# Sheet1.net
KiCad netlist of a schematic drawn in Altium Designer
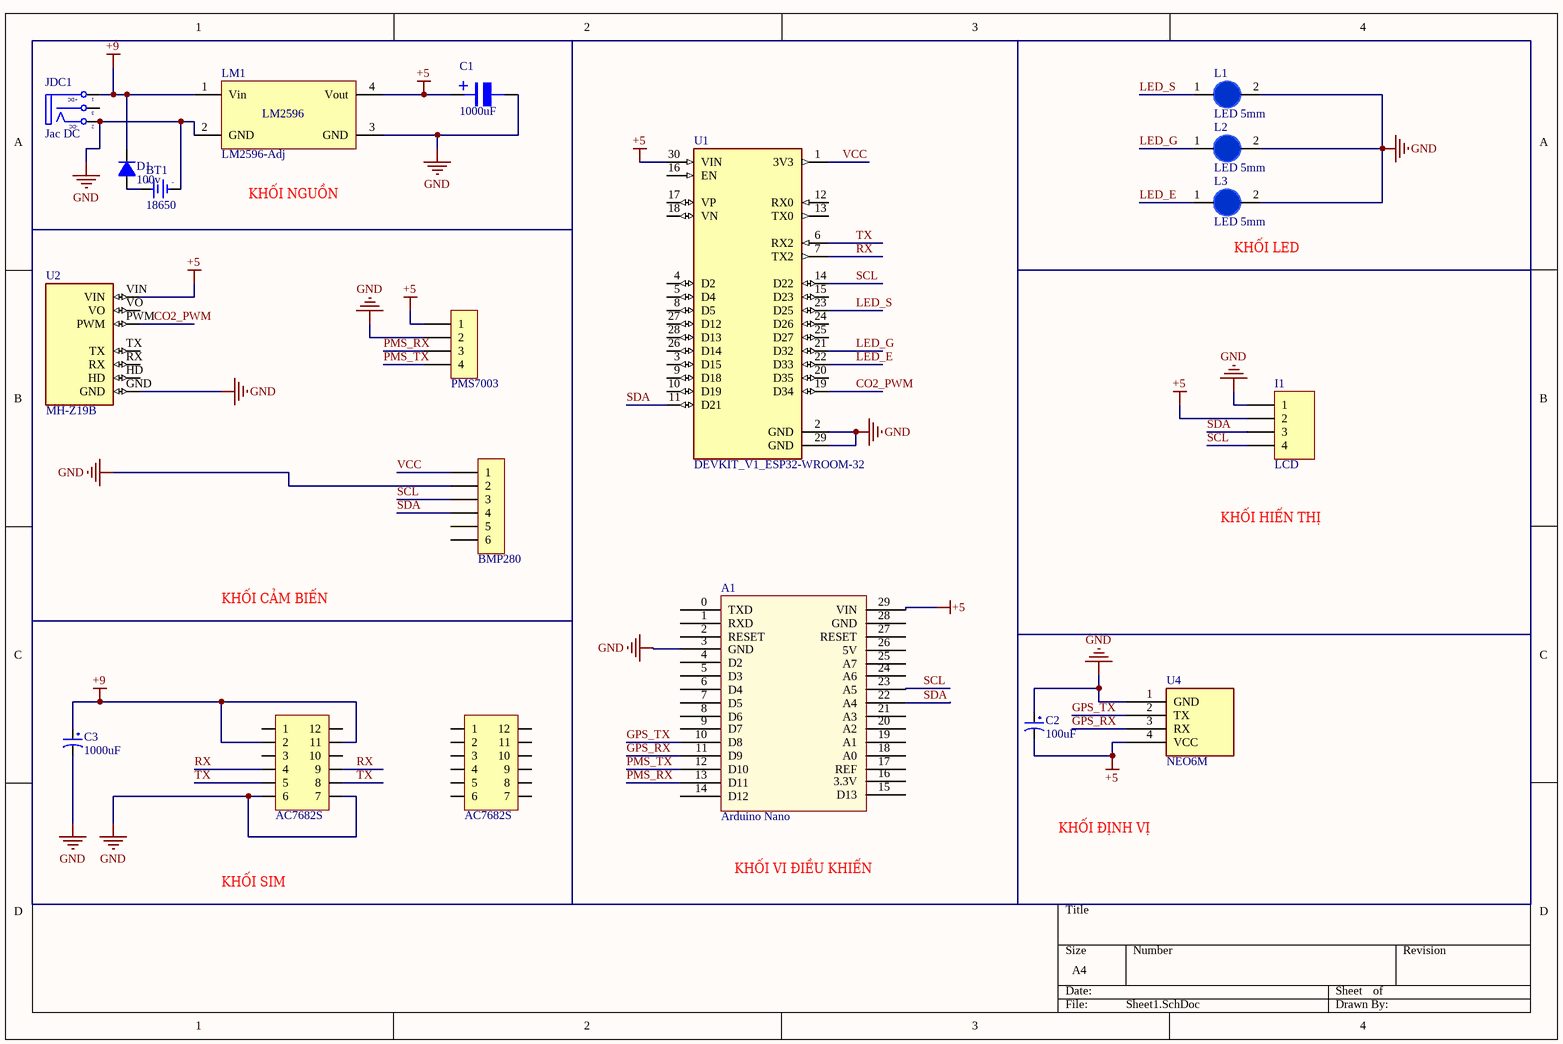
[diagram p0: Sheet1.SchDoc]

(export (version "E")
  (design (tool "Eeschema 10.0.6"))
  (components
    (comp (ref "A1")
      (value "Arduino Nano")
      (footprint "Arduino Nano")
      (libsource (lib "KhanhBK_Library_4") (part "Arduino Nano"))
    )
    (comp (ref "BT1")
      (value "18650")
      (footprint "DE PIN 18650 X2")
      (description "De Pin 18650 x2")
      (libsource (lib "Altium_Lib_by_KhueNguyenCreator") (part "De Pin 18650 x2"))
    )
    (comp (ref "C1")
      (value "1000uF")
      (footprint "tu nhom 10 (G)")
      (description "Dán")
      (libsource (lib "Altium_Lib_by_KhueNguyenCreator") (part "Tu Nhom 1000uF 16V"))
    )
    (comp (ref "C2")
      (value "100uF")
      (footprint "tu hoa 5mm")
      (description "Cắm")
      (libsource (lib "Altium_Lib_by_KhueNguyenCreator") (part "Tu Hoa 100uF 16V 5x11"))
    )
    (comp (ref "C3")
      (value "1000uF")
      (footprint "tu hoa 13mm")
      (description "Cắm")
      (libsource (lib "Altium_Lib_by_KhueNguyenCreator") (part "Tu Hoa 1000uF 25V 13x21"))
    )
    (comp (ref "D1")
      (value "100v")
      (footprint "DIODE 1A")
      (description "Cắm")
      (libsource (lib "Altium_Lib_by_KhueNguyenCreator") (part "Diode 1N4007"))
    )
    (comp (ref "H1")
      (value "PMS7003")
      (footprint "XH2.54M-4")
      (description "Cắm")
      (libsource (lib "Altium_Lib_by_KhueNguyenCreator") (part "Header 4P 2.54 Duc Thang"))
    )
    (comp (ref "H2")
      (value "BMP280")
      (footprint "Header 6P DC 2.54")
      (description "Cắm")
      (libsource (lib "Altium_Lib_by_KhueNguyenCreator") (part "Header 6P 2.54 Duc Cong"))
    )
    (comp (ref "I1")
      (value "LCD")
      (footprint "HEADER 4")
      (libsource (lib "KhanhBK_Library_4") (part "HEADER 4"))
    )
    (comp (ref "JDC1")
      (value "Jac DC")
      (footprint "DC-IN")
      (description "Jac DC input")
      (libsource (lib "syhaunguyen") (part "DCIN"))
    )
    (comp (ref "JP1")
      (value "AC7682S")
      (footprint "JP 2x6 CT")
      (description "Cắm")
      (libsource (lib "Altium_Lib_by_KhueNguyenCreator") (part "JP 2x6 2.54 Cai Thang"))
    )
    (comp (ref "JP2")
      (value "AC7682S")
      (footprint "JP 2x6 CT")
      (description "Cắm")
      (libsource (lib "Altium_Lib_by_KhueNguyenCreator") (part "JP 2x6 2.54 Cai Thang"))
    )
    (comp (ref "L1")
      (value "LED 5mm")
      (footprint "LED-5MM-BLUE")
      (description "Cắm")
      (libsource (lib "Altium_Lib_by_KhueNguyenCreator") (part "LED 5mm Xanh Duong"))
    )
    (comp (ref "L2")
      (value "LED 5mm")
      (footprint "LED-5MM-BLUE")
      (description "Cắm")
      (libsource (lib "Altium_Lib_by_KhueNguyenCreator") (part "LED 5mm Xanh Duong"))
    )
    (comp (ref "L3")
      (value "LED 5mm")
      (footprint "LED-5MM-BLUE")
      (description "Cắm")
      (libsource (lib "Altium_Lib_by_KhueNguyenCreator") (part "LED 5mm Xanh Duong"))
    )
    (comp (ref "LM1")
      (value "LM2596-Adj")
      (footprint "lm2596")
      (description "Designed By @Alixahedi")
      (libsource (lib "LM2596-Adj") (part "LM2596-Adj"))
    )
    (comp (ref "U1")
      (value "DEVKIT_V1_ESP32-WROOM-32")
      (footprint "MODULE_DEVKIT_V1_ESP32-WROOM-32")
      (description "WROOM-32 Development Board ESP32 ESP-32S WiFi Bluetooth Dev Module")
      (fields (field (name "MF") "Do it") (field (name "MP") "DEVKIT V1 ESP32-WROOM-32"))
      (libsource (lib "DEVKIT_V1_ESP32-WROOM-32") (part "DEVKIT_V1_ESP32-WROOM-32"))
    )
    (comp (ref "U2")
      (value "MH-Z19B")
      (footprint "MH-Z19B")
      (description "Intelligent Infrared CO2 Module")
      (fields (field (name "MF") "Winsen"))
      (libsource (lib "MH-Z19B") (part "MH-Z19B"))
    )
    (comp (ref "U4") (value "NEO6M") (footprint "NEO6M") (libsource (lib "Sensors") (part "NEO6M")))
  )
  (nets
    (net (code "1") (name "+5") (class "Default")
      (node (ref "A1") (pin "29") (pinfunction "VIN_29") (pintype "passive"))
      (node (ref "C1") (pin "1") (pinfunction "1_1") (pintype "passive"))
      (node (ref "C2") (pin "2") (pinfunction "2_2") (pintype "passive"))
      (node (ref "H1") (pin "1") (pinfunction "1_1") (pintype "passive"))
      (node (ref "I1") (pin "2") (pinfunction "2_2") (pintype "passive"))
      (node (ref "LM1") (pin "4") (pinfunction "Vout_4") (pintype "passive"))
      (node (ref "U1") (pin "30") (pinfunction "VIN_30") (pintype "input"))
      (node (ref "U2") (pin "VIN") (pinfunction "VIN_VIN") (pintype "bidirectional"))
      (node (ref "U4") (pin "4") (pinfunction "VCC_4") (pintype "passive"))
    )
    (net (code "2") (name "+9") (class "Default")
      (node (ref "C3") (pin "1") (pinfunction "1_1") (pintype "passive"))
      (node (ref "D1") (pin "2") (pinfunction "K_2") (pintype "passive"))
      (node (ref "JDC1") (pin "1") (pinfunction "T_1") (pintype "passive"))
      (node (ref "JP2") (pin "11") (pinfunction "11_11") (pintype "passive"))
      (node (ref "JP2") (pin "2") (pinfunction "2_2") (pintype "passive"))
      (node (ref "LM1") (pin "1") (pinfunction "Vin_1") (pintype "passive"))
    )
    (net (code "3") (name "/CO2_PWM") (class "Default")
      (node (ref "U1") (pin "19") (pinfunction "D34_19") (pintype "bidirectional"))
      (node (ref "U2") (pin "PWM") (pinfunction "PWM_PWM") (pintype "bidirectional"))
    )
    (net (code "4") (name "/GPS_RX") (class "Default")
      (node (ref "A1") (pin "11") (pinfunction "D9_11") (pintype "passive"))
      (node (ref "U4") (pin "3") (pinfunction "RX_3") (pintype "passive"))
    )
    (net (code "5") (name "/GPS_TX") (class "Default")
      (node (ref "A1") (pin "10") (pinfunction "D8_10") (pintype "passive"))
      (node (ref "U4") (pin "2") (pinfunction "TX_2") (pintype "passive"))
    )
    (net (code "6") (name "/LED_E") (class "Default")
      (node (ref "L3") (pin "1") (pinfunction "A_1") (pintype "passive"))
      (node (ref "U1") (pin "22") (pinfunction "D33_22") (pintype "bidirectional"))
    )
    (net (code "7") (name "/LED_G") (class "Default")
      (node (ref "L2") (pin "1") (pinfunction "A_1") (pintype "passive"))
      (node (ref "U1") (pin "21") (pinfunction "D32_21") (pintype "bidirectional"))
    )
    (net (code "8") (name "/LED_S") (class "Default")
      (node (ref "L1") (pin "1") (pinfunction "A_1") (pintype "passive"))
      (node (ref "U1") (pin "23") (pinfunction "D25_23") (pintype "bidirectional"))
    )
    (net (code "9") (name "/PMS_RX") (class "Default")
      (node (ref "A1") (pin "13") (pinfunction "D11_13") (pintype "passive"))
      (node (ref "H1") (pin "3") (pinfunction "3_3") (pintype "passive"))
    )
    (net (code "10") (name "/PMS_TX") (class "Default")
      (node (ref "A1") (pin "12") (pinfunction "D10_12") (pintype "passive"))
      (node (ref "H1") (pin "4") (pinfunction "4_4") (pintype "passive"))
    )
    (net (code "11") (name "/RX") (class "Default")
      (node (ref "JP2") (pin "4") (pinfunction "4_4") (pintype "passive"))
      (node (ref "JP2") (pin "9") (pinfunction "9_9") (pintype "passive"))
      (node (ref "U1") (pin "7") (pinfunction "TX2_7") (pintype "output"))
    )
    (net (code "12") (name "/SCL") (class "Default")
      (node (ref "A1") (pin "23") (pinfunction "A5_23") (pintype "passive"))
      (node (ref "H2") (pin "3") (pinfunction "3_3") (pintype "passive"))
      (node (ref "I1") (pin "4") (pinfunction "4_4") (pintype "passive"))
      (node (ref "U1") (pin "14") (pinfunction "D22_14") (pintype "bidirectional"))
    )
    (net (code "13") (name "/SDA") (class "Default")
      (node (ref "A1") (pin "22") (pinfunction "A4_22") (pintype "passive"))
      (node (ref "H2") (pin "4") (pinfunction "4_4") (pintype "passive"))
      (node (ref "I1") (pin "3") (pinfunction "3_3") (pintype "passive"))
      (node (ref "U1") (pin "11") (pinfunction "D21_11") (pintype "bidirectional"))
    )
    (net (code "14") (name "/TX") (class "Default")
      (node (ref "JP2") (pin "5") (pinfunction "5_5") (pintype "passive"))
      (node (ref "JP2") (pin "8") (pinfunction "8_8") (pintype "passive"))
      (node (ref "U1") (pin "6") (pinfunction "RX2_6") (pintype "input"))
    )
    (net (code "15") (name "/VCC") (class "Default")
      (node (ref "H2") (pin "1") (pinfunction "1_1") (pintype "passive"))
      (node (ref "U1") (pin "1") (pinfunction "3V3_1") (pintype "output"))
    )
    (net (code "16") (name "GND") (class "Default")
      (node (ref "A1") (pin "3") (pinfunction "GND_3") (pintype "passive"))
      (node (ref "BT1") (pin "2") (pinfunction "GND_2") (pintype "passive"))
      (node (ref "C1") (pin "2") (pinfunction "2_2") (pintype "passive"))
      (node (ref "C2") (pin "1") (pinfunction "1_1") (pintype "passive"))
      (node (ref "C3") (pin "2") (pinfunction "2_2") (pintype "passive"))
      (node (ref "H1") (pin "2") (pinfunction "2_2") (pintype "passive"))
      (node (ref "H2") (pin "2") (pinfunction "2_2") (pintype "passive"))
      (node (ref "I1") (pin "1") (pinfunction "1_1") (pintype "passive"))
      (node (ref "JDC1") (pin "2") (pinfunction "TN_2") (pintype "passive"))
      (node (ref "JP2") (pin "6") (pinfunction "6_6") (pintype "passive"))
      (node (ref "JP2") (pin "7") (pinfunction "7_7") (pintype "passive"))
      (node (ref "L1") (pin "2") (pinfunction "K_2") (pintype "passive"))
      (node (ref "L2") (pin "2") (pinfunction "K_2") (pintype "passive"))
      (node (ref "L3") (pin "2") (pinfunction "K_2") (pintype "passive"))
      (node (ref "LM1") (pin "2") (pinfunction "GND_2") (pintype "passive"))
      (node (ref "LM1") (pin "3") (pinfunction "GND_3") (pintype "passive"))
      (node (ref "U1") (pin "2") (pinfunction "GND_2") (pintype "power_in"))
      (node (ref "U1") (pin "29") (pinfunction "GND_29") (pintype "power_in"))
      (node (ref "U2") (pin "GND") (pinfunction "GND_GND") (pintype "bidirectional"))
      (node (ref "U4") (pin "1") (pinfunction "GND_1") (pintype "passive"))
    )
    (net (code "17") (name "Net-(BT1-+3V)") (class "Default")
      (node (ref "BT1") (pin "1") (pinfunction "+3V_1") (pintype "passive"))
      (node (ref "D1") (pin "1") (pinfunction "A_1") (pintype "passive"))
    )
    (net (code "18") (name "unconnected-(A1-3.3V-Pad16)") (class "Default")
      (node (ref "A1") (pin "16") (pinfunction "3.3V_16") (pintype "passive"))
    )
    (net (code "19") (name "unconnected-(A1-5V-Pad26)") (class "Default")
      (node (ref "A1") (pin "26") (pinfunction "5V_26") (pintype "passive"))
    )
    (net (code "20") (name "unconnected-(A1-A0-Pad18)") (class "Default")
      (node (ref "A1") (pin "18") (pinfunction "A0_18") (pintype "passive"))
    )
    (net (code "21") (name "unconnected-(A1-A1-Pad19)") (class "Default")
      (node (ref "A1") (pin "19") (pinfunction "A1_19") (pintype "passive"))
    )
    (net (code "22") (name "unconnected-(A1-A2-Pad20)") (class "Default")
      (node (ref "A1") (pin "20") (pinfunction "A2_20") (pintype "passive"))
    )
    (net (code "23") (name "unconnected-(A1-A3-Pad21)") (class "Default")
      (node (ref "A1") (pin "21") (pinfunction "A3_21") (pintype "passive"))
    )
    (net (code "24") (name "unconnected-(A1-A6-Pad24)") (class "Default")
      (node (ref "A1") (pin "24") (pinfunction "A6_24") (pintype "passive"))
    )
    (net (code "25") (name "unconnected-(A1-A7-Pad25)") (class "Default")
      (node (ref "A1") (pin "25") (pinfunction "A7_25") (pintype "passive"))
    )
    (net (code "26") (name "unconnected-(A1-D2-Pad4)") (class "Default")
      (node (ref "A1") (pin "4") (pinfunction "D2_4") (pintype "passive"))
    )
    (net (code "27") (name "unconnected-(A1-D3-Pad5)") (class "Default")
      (node (ref "A1") (pin "5") (pinfunction "D3_5") (pintype "passive"))
    )
    (net (code "28") (name "unconnected-(A1-D4-Pad6)") (class "Default")
      (node (ref "A1") (pin "6") (pinfunction "D4_6") (pintype "passive"))
    )
    (net (code "29") (name "unconnected-(A1-D5-Pad7)") (class "Default")
      (node (ref "A1") (pin "7") (pinfunction "D5_7") (pintype "passive"))
    )
    (net (code "30") (name "unconnected-(A1-D6-Pad8)") (class "Default")
      (node (ref "A1") (pin "8") (pinfunction "D6_8") (pintype "passive"))
    )
    (net (code "31") (name "unconnected-(A1-D7-Pad9)") (class "Default")
      (node (ref "A1") (pin "9") (pinfunction "D7_9") (pintype "passive"))
    )
    (net (code "32") (name "unconnected-(A1-D12-Pad14)") (class "Default")
      (node (ref "A1") (pin "14") (pinfunction "D12_14") (pintype "passive"))
    )
    (net (code "33") (name "unconnected-(A1-D13-Pad15)") (class "Default")
      (node (ref "A1") (pin "15") (pinfunction "D13_15") (pintype "passive"))
    )
    (net (code "34") (name "unconnected-(A1-GND-Pad28)") (class "Default")
      (node (ref "A1") (pin "28") (pinfunction "GND_28") (pintype "passive"))
    )
    (net (code "35") (name "unconnected-(A1-REF-Pad17)") (class "Default")
      (node (ref "A1") (pin "17") (pinfunction "REF_17") (pintype "passive"))
    )
    (net (code "36") (name "unconnected-(A1-RESET-Pad2)") (class "Default")
      (node (ref "A1") (pin "2") (pinfunction "RESET_2") (pintype "passive"))
    )
    (net (code "37") (name "unconnected-(A1-RESET-Pad27)") (class "Default")
      (node (ref "A1") (pin "27") (pinfunction "RESET_27") (pintype "passive"))
    )
    (net (code "38") (name "unconnected-(A1-RXD-Pad1)") (class "Default")
      (node (ref "A1") (pin "1") (pinfunction "RXD_1") (pintype "passive"))
    )
    (net (code "39") (name "unconnected-(A1-TXD-Pad0)") (class "Default")
      (node (ref "A1") (pin "0") (pinfunction "TXD_0") (pintype "passive"))
    )
    (net (code "40") (name "unconnected-(H2-Pad5)") (class "Default")
      (node (ref "H2") (pin "5") (pinfunction "5_5") (pintype "passive"))
    )
    (net (code "41") (name "unconnected-(H2-Pad6)") (class "Default")
      (node (ref "H2") (pin "6") (pinfunction "6_6") (pintype "passive"))
    )
    (net (code "42") (name "unconnected-(JDC1-S-Pad3)") (class "Default")
      (node (ref "JDC1") (pin "3") (pinfunction "S_3") (pintype "power_in"))
    )
    (net (code "43") (name "unconnected-(JP1-Pad1)") (class "Default")
      (node (ref "JP1") (pin "1") (pinfunction "1_1") (pintype "passive"))
    )
    (net (code "44") (name "unconnected-(JP1-Pad2)") (class "Default")
      (node (ref "JP1") (pin "2") (pinfunction "2_2") (pintype "passive"))
    )
    (net (code "45") (name "unconnected-(JP1-Pad3)") (class "Default")
      (node (ref "JP1") (pin "3") (pinfunction "3_3") (pintype "passive"))
    )
    (net (code "46") (name "unconnected-(JP1-Pad4)") (class "Default")
      (node (ref "JP1") (pin "4") (pinfunction "4_4") (pintype "passive"))
    )
    (net (code "47") (name "unconnected-(JP1-Pad5)") (class "Default")
      (node (ref "JP1") (pin "5") (pinfunction "5_5") (pintype "passive"))
    )
    (net (code "48") (name "unconnected-(JP1-Pad6)") (class "Default")
      (node (ref "JP1") (pin "6") (pinfunction "6_6") (pintype "passive"))
    )
    (net (code "49") (name "unconnected-(JP1-Pad7)") (class "Default")
      (node (ref "JP1") (pin "7") (pinfunction "7_7") (pintype "passive"))
    )
    (net (code "50") (name "unconnected-(JP1-Pad8)") (class "Default")
      (node (ref "JP1") (pin "8") (pinfunction "8_8") (pintype "passive"))
    )
    (net (code "51") (name "unconnected-(JP1-Pad9)") (class "Default")
      (node (ref "JP1") (pin "9") (pinfunction "9_9") (pintype "passive"))
    )
    (net (code "52") (name "unconnected-(JP1-Pad10)") (class "Default")
      (node (ref "JP1") (pin "10") (pinfunction "10_10") (pintype "passive"))
    )
    (net (code "53") (name "unconnected-(JP1-Pad11)") (class "Default")
      (node (ref "JP1") (pin "11") (pinfunction "11_11") (pintype "passive"))
    )
    (net (code "54") (name "unconnected-(JP1-Pad12)") (class "Default")
      (node (ref "JP1") (pin "12") (pinfunction "12_12") (pintype "passive"))
    )
    (net (code "55") (name "unconnected-(JP2-Pad1)") (class "Default")
      (node (ref "JP2") (pin "1") (pinfunction "1_1") (pintype "passive"))
    )
    (net (code "56") (name "unconnected-(JP2-Pad3)") (class "Default")
      (node (ref "JP2") (pin "3") (pinfunction "3_3") (pintype "passive"))
    )
    (net (code "57") (name "unconnected-(JP2-Pad10)") (class "Default")
      (node (ref "JP2") (pin "10") (pinfunction "10_10") (pintype "passive"))
    )
    (net (code "58") (name "unconnected-(JP2-Pad12)") (class "Default")
      (node (ref "JP2") (pin "12") (pinfunction "12_12") (pintype "passive"))
    )
    (net (code "59") (name "unconnected-(U1-D2-Pad4)") (class "Default")
      (node (ref "U1") (pin "4") (pinfunction "D2_4") (pintype "bidirectional"))
    )
    (net (code "60") (name "unconnected-(U1-D4-Pad5)") (class "Default")
      (node (ref "U1") (pin "5") (pinfunction "D4_5") (pintype "bidirectional"))
    )
    (net (code "61") (name "unconnected-(U1-D5-Pad8)") (class "Default")
      (node (ref "U1") (pin "8") (pinfunction "D5_8") (pintype "bidirectional"))
    )
    (net (code "62") (name "unconnected-(U1-D12-Pad27)") (class "Default")
      (node (ref "U1") (pin "27") (pinfunction "D12_27") (pintype "bidirectional"))
    )
    (net (code "63") (name "unconnected-(U1-D13-Pad28)") (class "Default")
      (node (ref "U1") (pin "28") (pinfunction "D13_28") (pintype "bidirectional"))
    )
    (net (code "64") (name "unconnected-(U1-D14-Pad26)") (class "Default")
      (node (ref "U1") (pin "26") (pinfunction "D14_26") (pintype "bidirectional"))
    )
    (net (code "65") (name "unconnected-(U1-D15-Pad3)") (class "Default")
      (node (ref "U1") (pin "3") (pinfunction "D15_3") (pintype "bidirectional"))
    )
    (net (code "66") (name "unconnected-(U1-D18-Pad9)") (class "Default")
      (node (ref "U1") (pin "9") (pinfunction "D18_9") (pintype "bidirectional"))
    )
    (net (code "67") (name "unconnected-(U1-D19-Pad10)") (class "Default")
      (node (ref "U1") (pin "10") (pinfunction "D19_10") (pintype "bidirectional"))
    )
    (net (code "68") (name "unconnected-(U1-D23-Pad15)") (class "Default")
      (node (ref "U1") (pin "15") (pinfunction "D23_15") (pintype "bidirectional"))
    )
    (net (code "69") (name "unconnected-(U1-D26-Pad24)") (class "Default")
      (node (ref "U1") (pin "24") (pinfunction "D26_24") (pintype "bidirectional"))
    )
    (net (code "70") (name "unconnected-(U1-D27-Pad25)") (class "Default")
      (node (ref "U1") (pin "25") (pinfunction "D27_25") (pintype "bidirectional"))
    )
    (net (code "71") (name "unconnected-(U1-D35-Pad20)") (class "Default")
      (node (ref "U1") (pin "20") (pinfunction "D35_20") (pintype "bidirectional"))
    )
    (net (code "72") (name "unconnected-(U1-EN-Pad16)") (class "Default")
      (node (ref "U1") (pin "16") (pinfunction "EN_16") (pintype "input"))
    )
    (net (code "73") (name "unconnected-(U1-RX0-Pad12)") (class "Default")
      (node (ref "U1") (pin "12") (pinfunction "RX0_12") (pintype "input"))
    )
    (net (code "74") (name "unconnected-(U1-TX0-Pad13)") (class "Default")
      (node (ref "U1") (pin "13") (pinfunction "TX0_13") (pintype "output"))
    )
    (net (code "75") (name "unconnected-(U1-VN-Pad18)") (class "Default")
      (node (ref "U1") (pin "18") (pinfunction "VN_18") (pintype "bidirectional"))
    )
    (net (code "76") (name "unconnected-(U1-VP-Pad17)") (class "Default")
      (node (ref "U1") (pin "17") (pinfunction "VP_17") (pintype "bidirectional"))
    )
    (net (code "77") (name "unconnected-(U2-PadHD)") (class "Default")
      (node (ref "U2") (pin "HD") (pinfunction "HD_HD") (pintype "bidirectional"))
    )
    (net (code "78") (name "unconnected-(U2-PadRX)") (class "Default")
      (node (ref "U2") (pin "RX") (pinfunction "RX_RX") (pintype "bidirectional"))
    )
    (net (code "79") (name "unconnected-(U2-PadTX)") (class "Default")
      (node (ref "U2") (pin "TX") (pinfunction "TX_TX") (pintype "bidirectional"))
    )
    (net (code "80") (name "unconnected-(U2-PadVO)") (class "Default")
      (node (ref "U2") (pin "VO") (pinfunction "VO_VO") (pintype "bidirectional"))
    )
  )
)
